# SensingSchDoc.net
KiCad netlist of a schematic drawn in Altium Designer
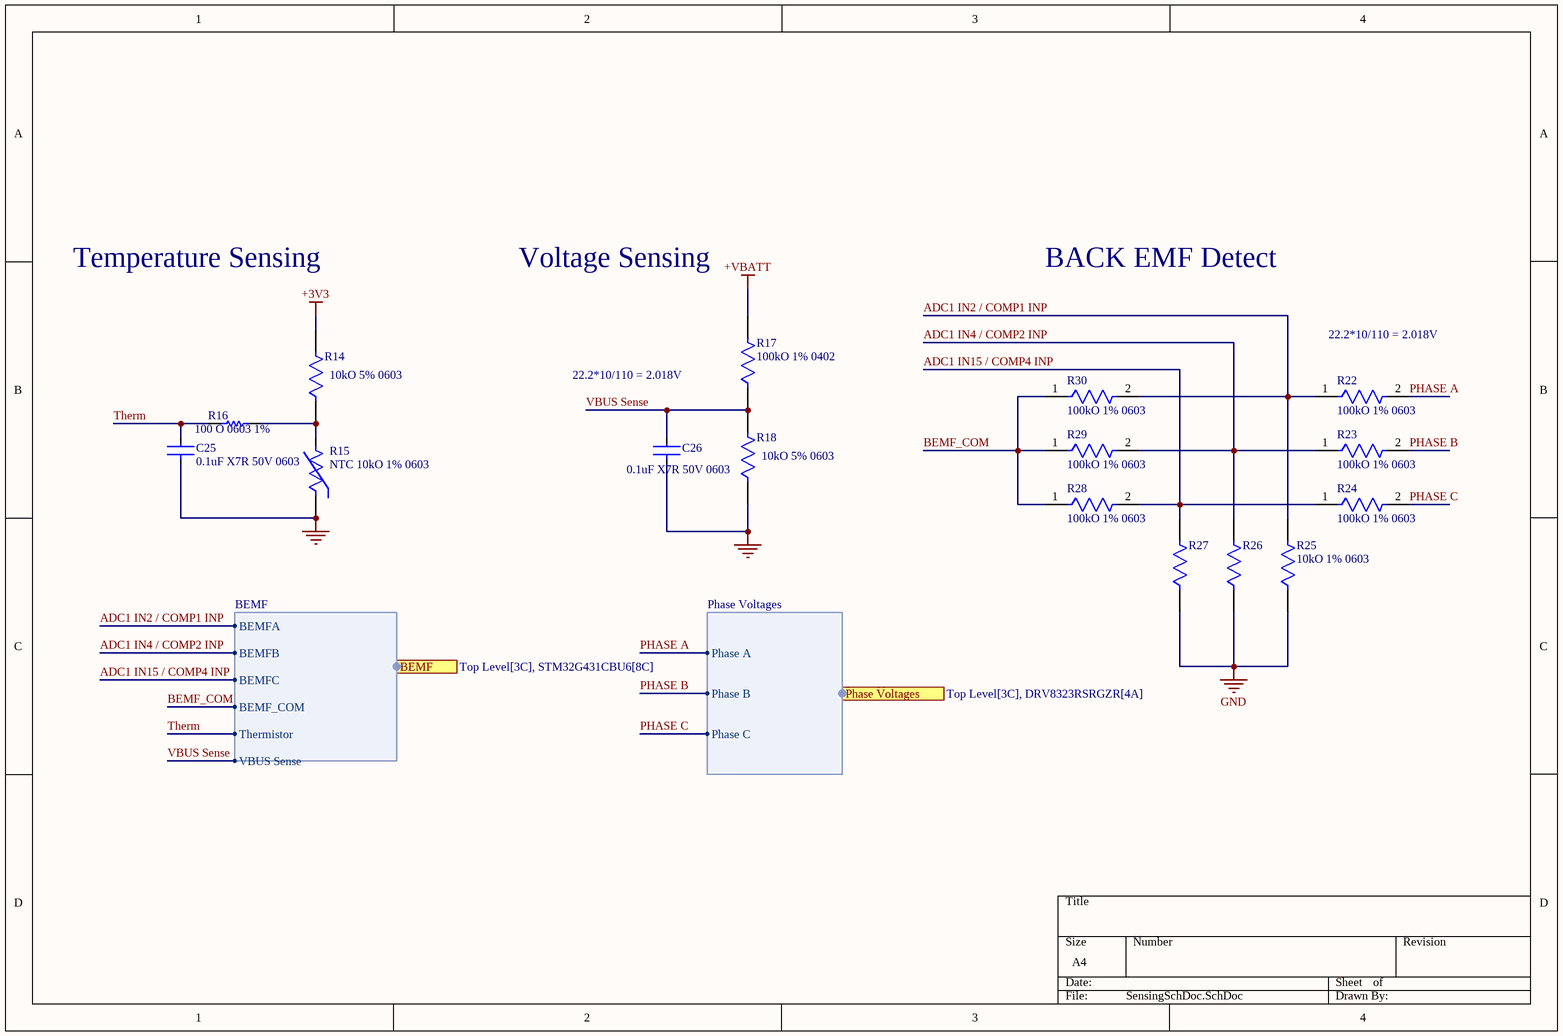
[diagram p0: SensingSchDoc.SchDoc]

(export (version "E")
  (design (tool "Eeschema 10.0.6"))
  (components
    (comp (ref "C25")
      (value "0.1uF X7R 50V 0603")
      (footprint "FP-0603B104K500CT-IPC_C")
      (description "CAP CER 0.1UF 50V X7R 0603")
      (fields (field (name "TOLERANCE") "10%"))
      (libsource (lib "Altium Content Vault") (part "02cd4be3c70576c341d710602a673aa"))
    )
    (comp (ref "C26")
      (value "0.1uF X7R 50V 0603")
      (footprint "FP-0603B104K500CT-IPC_C")
      (description "CAP CER 0.1UF 50V X7R 0603")
      (fields (field (name "TOLERANCE") "10%"))
      (libsource (lib "Altium Content Vault") (part "02cd4be3c70576c341d710602a673aa"))
    )
    (comp (ref "R14")
      (value "10kO 5% 0603")
      (footprint "FP-AC0603-IPC_A")
      (description "RES 10kΩ 5.00% 0.2W 0603")
      (libsource (lib "") (part "1029c3af85768c4190bb7ad29bc67b5_1"))
    )
    (comp (ref "R15")
      (value "NTC 10kO 1% 0603")
      (footprint "FP-NCP18-0_15-IPC_A")
      (description "NTC Thermistor for Temperature Sensor, 0603, 10kΩ, 1%, 0.1mA, 5V")
      (fields (field (name "TOLERANCE") "1%"))
      (libsource (lib "Altium Content Vault") (part "3b148a6ebabc5fb4d708a66c052d352"))
    )
    (comp (ref "R16")
      (value "100 O 0603 1%")
      (footprint "RESC1608X55X25ML10T15")
      (fields (field (name "PART NUMBER") "RC0603FR-10100RL") (field (name "MANUFACTURER") "Yageo"))
      (libsource (lib "Altium Content Vault") (part "RES"))
    )
    (comp (ref "R17")
      (value "100kO 1% 0402")
      (footprint "FP-CRGP0402-IPC_C")
      (description "SMD Precision Pulse Thick Film Chip Resistor")
      (fields
        (field (name "OCTOPART") "https://octopart.com/crgp0402f100k-te+connectivity-91018658")
        (field (name "TOLERANCE") "0.01")
      )
      (libsource (lib "") (part "1029c3af85768c4190bb7ad29bc67b5_1"))
    )
    (comp (ref "R18")
      (value "10kO 5% 0603")
      (footprint "FP-AC0603-IPC_A")
      (description "RES 10kΩ 5.00% 0.2W 0603")
      (libsource (lib "") (part "1029c3af85768c4190bb7ad29bc67b5_1"))
    )
    (comp (ref "R22")
      (value "100kO 1% 0603")
      (footprint "FP-RT0603-MFG")
      (description "RT0603 100KΩ 0.1W 50 ppm/°C 1.00%")
      (fields (field (name "MANUFACTURER PART NUMBER") "RT0603FRE13100KL") (field (name "TOLERANCE") "0.01"))
      (libsource (lib "Altium Content Vault") (part "1029c3af85768c4190bb7ad29bc67b5"))
    )
    (comp (ref "R23")
      (value "100kO 1% 0603")
      (footprint "FP-RT0603-MFG")
      (description "RT0603 100KΩ 0.1W 50 ppm/°C 1.00%")
      (fields (field (name "MANUFACTURER PART NUMBER") "RT0603FRE13100KL") (field (name "TOLERANCE") "0.01"))
      (libsource (lib "Altium Content Vault") (part "1029c3af85768c4190bb7ad29bc67b5"))
    )
    (comp (ref "R24")
      (value "100kO 1% 0603")
      (footprint "FP-RT0603-MFG")
      (description "RT0603 100KΩ 0.1W 50 ppm/°C 1.00%")
      (fields (field (name "MANUFACTURER PART NUMBER") "RT0603FRE13100KL") (field (name "TOLERANCE") "0.01"))
      (libsource (lib "Altium Content Vault") (part "1029c3af85768c4190bb7ad29bc67b5"))
    )
    (comp (ref "R25")
      (value "10kO 1% 0603")
      (footprint "FP-MCT0603-IPC_C")
      (description "RES SMD 100 OHM 1% 1/8W 0603")
      (fields (field (name "TOLERANCE") "1%"))
      (libsource (lib "") (part "1029c3af85768c4190bb7ad29bc67b5_1"))
    )
    (comp (ref "R26")
      (value "10kO 1% 0603")
      (footprint "FP-MCT0603-IPC_C")
      (description "RES SMD 100 OHM 1% 1/8W 0603")
      (fields (field (name "TOLERANCE") "1%"))
      (libsource (lib "") (part "1029c3af85768c4190bb7ad29bc67b5_1"))
    )
    (comp (ref "R27")
      (value "10kO 1% 0603")
      (footprint "FP-MCT0603-IPC_C")
      (description "RES SMD 100 OHM 1% 1/8W 0603")
      (fields (field (name "TOLERANCE") "1%"))
      (libsource (lib "") (part "1029c3af85768c4190bb7ad29bc67b5_1"))
    )
    (comp (ref "R28")
      (value "100kO 1% 0603")
      (footprint "FP-RT0603-MFG")
      (description "RT0603 100KΩ 0.1W 50 ppm/°C 1.00%")
      (fields (field (name "MANUFACTURER PART NUMBER") "RT0603FRE13100KL") (field (name "TOLERANCE") "0.01"))
      (libsource (lib "Altium Content Vault") (part "1029c3af85768c4190bb7ad29bc67b5"))
    )
    (comp (ref "R29")
      (value "100kO 1% 0603")
      (footprint "FP-RT0603-MFG")
      (description "RT0603 100KΩ 0.1W 50 ppm/°C 1.00%")
      (fields (field (name "MANUFACTURER PART NUMBER") "RT0603FRE13100KL") (field (name "TOLERANCE") "0.01"))
      (libsource (lib "Altium Content Vault") (part "1029c3af85768c4190bb7ad29bc67b5"))
    )
    (comp (ref "R30")
      (value "100kO 1% 0603")
      (footprint "FP-RT0603-MFG")
      (description "RT0603 100KΩ 0.1W 50 ppm/°C 1.00%")
      (fields (field (name "MANUFACTURER PART NUMBER") "RT0603FRE13100KL") (field (name "TOLERANCE") "0.01"))
      (libsource (lib "Altium Content Vault") (part "1029c3af85768c4190bb7ad29bc67b5"))
    )
  )
  (nets
    (net (code "4") (name "+3V3") (class "Default")
      (node (ref "R14") (pin "2") (pinfunction "2_2") (pintype "passive"))
    )
    (net (code "5") (name "+VBATT") (class "Default")
      (node (ref "R17") (pin "2") (pinfunction "2_2") (pintype "passive"))
    )
    (net (code "6") (name "/ADC1 IN2 {slash} COMP1 INP") (class "Default")
      (node (ref "R22") (pin "1") (pinfunction "1_1") (pintype "passive"))
      (node (ref "R25") (pin "2") (pinfunction "2_2") (pintype "passive"))
      (node (ref "R30") (pin "2") (pinfunction "2_2") (pintype "passive"))
    )
    (net (code "7") (name "/ADC1 IN4 {slash} COMP2 INP") (class "Default")
      (node (ref "R23") (pin "1") (pinfunction "1_1") (pintype "passive"))
      (node (ref "R26") (pin "2") (pinfunction "2_2") (pintype "passive"))
      (node (ref "R29") (pin "2") (pinfunction "2_2") (pintype "passive"))
    )
    (net (code "8") (name "/ADC1 IN15 {slash} COMP4 INP") (class "Default")
      (node (ref "R24") (pin "1") (pinfunction "1_1") (pintype "passive"))
      (node (ref "R27") (pin "2") (pinfunction "2_2") (pintype "passive"))
      (node (ref "R28") (pin "2") (pinfunction "2_2") (pintype "passive"))
    )
    (net (code "9") (name "/BEMF_COM") (class "Default")
      (node (ref "R28") (pin "1") (pinfunction "1_1") (pintype "passive"))
      (node (ref "R29") (pin "1") (pinfunction "1_1") (pintype "passive"))
      (node (ref "R30") (pin "1") (pinfunction "1_1") (pintype "passive"))
    )
    (net (code "10") (name "/PHASE A") (class "Default")
      (node (ref "R22") (pin "2") (pinfunction "2_2") (pintype "passive"))
    )
    (net (code "11") (name "/PHASE B") (class "Default")
      (node (ref "R23") (pin "2") (pinfunction "2_2") (pintype "passive"))
    )
    (net (code "12") (name "/PHASE C") (class "Default")
      (node (ref "R24") (pin "2") (pinfunction "2_2") (pintype "passive"))
    )
    (net (code "13") (name "/Therm") (class "Default")
      (node (ref "C25") (pin "2") (pinfunction "2_2") (pintype "passive"))
      (node (ref "R16") (pin "1") (pinfunction "1_1") (pintype "passive"))
    )
    (net (code "14") (name "/VBUS Sense") (class "Default")
      (node (ref "C26") (pin "2") (pinfunction "2_2") (pintype "passive"))
      (node (ref "R17") (pin "1") (pinfunction "1_1") (pintype "passive"))
      (node (ref "R18") (pin "2") (pinfunction "2_2") (pintype "passive"))
    )
    (net (code "17") (name "GND") (class "Default")
      (node (ref "C25") (pin "1") (pinfunction "1_1") (pintype "passive"))
      (node (ref "C26") (pin "1") (pinfunction "1_1") (pintype "passive"))
      (node (ref "R15") (pin "1") (pinfunction "1_1") (pintype "passive"))
      (node (ref "R18") (pin "1") (pinfunction "1_1") (pintype "passive"))
      (node (ref "R25") (pin "1") (pinfunction "1_1") (pintype "passive"))
      (node (ref "R26") (pin "1") (pinfunction "1_1") (pintype "passive"))
      (node (ref "R27") (pin "1") (pinfunction "1_1") (pintype "passive"))
    )
    (net (code "18") (name "Net-(R14-Pad1)") (class "Default")
      (node (ref "R14") (pin "1") (pinfunction "1_1") (pintype "passive"))
      (node (ref "R15") (pin "2") (pinfunction "2_2") (pintype "passive"))
      (node (ref "R16") (pin "2") (pinfunction "2_2") (pintype "passive"))
    )
  )
)
